# arduinoRGBkaleidoscopeCkt1_v4.net
KiCad netlist of a schematic drawn in EAGLE
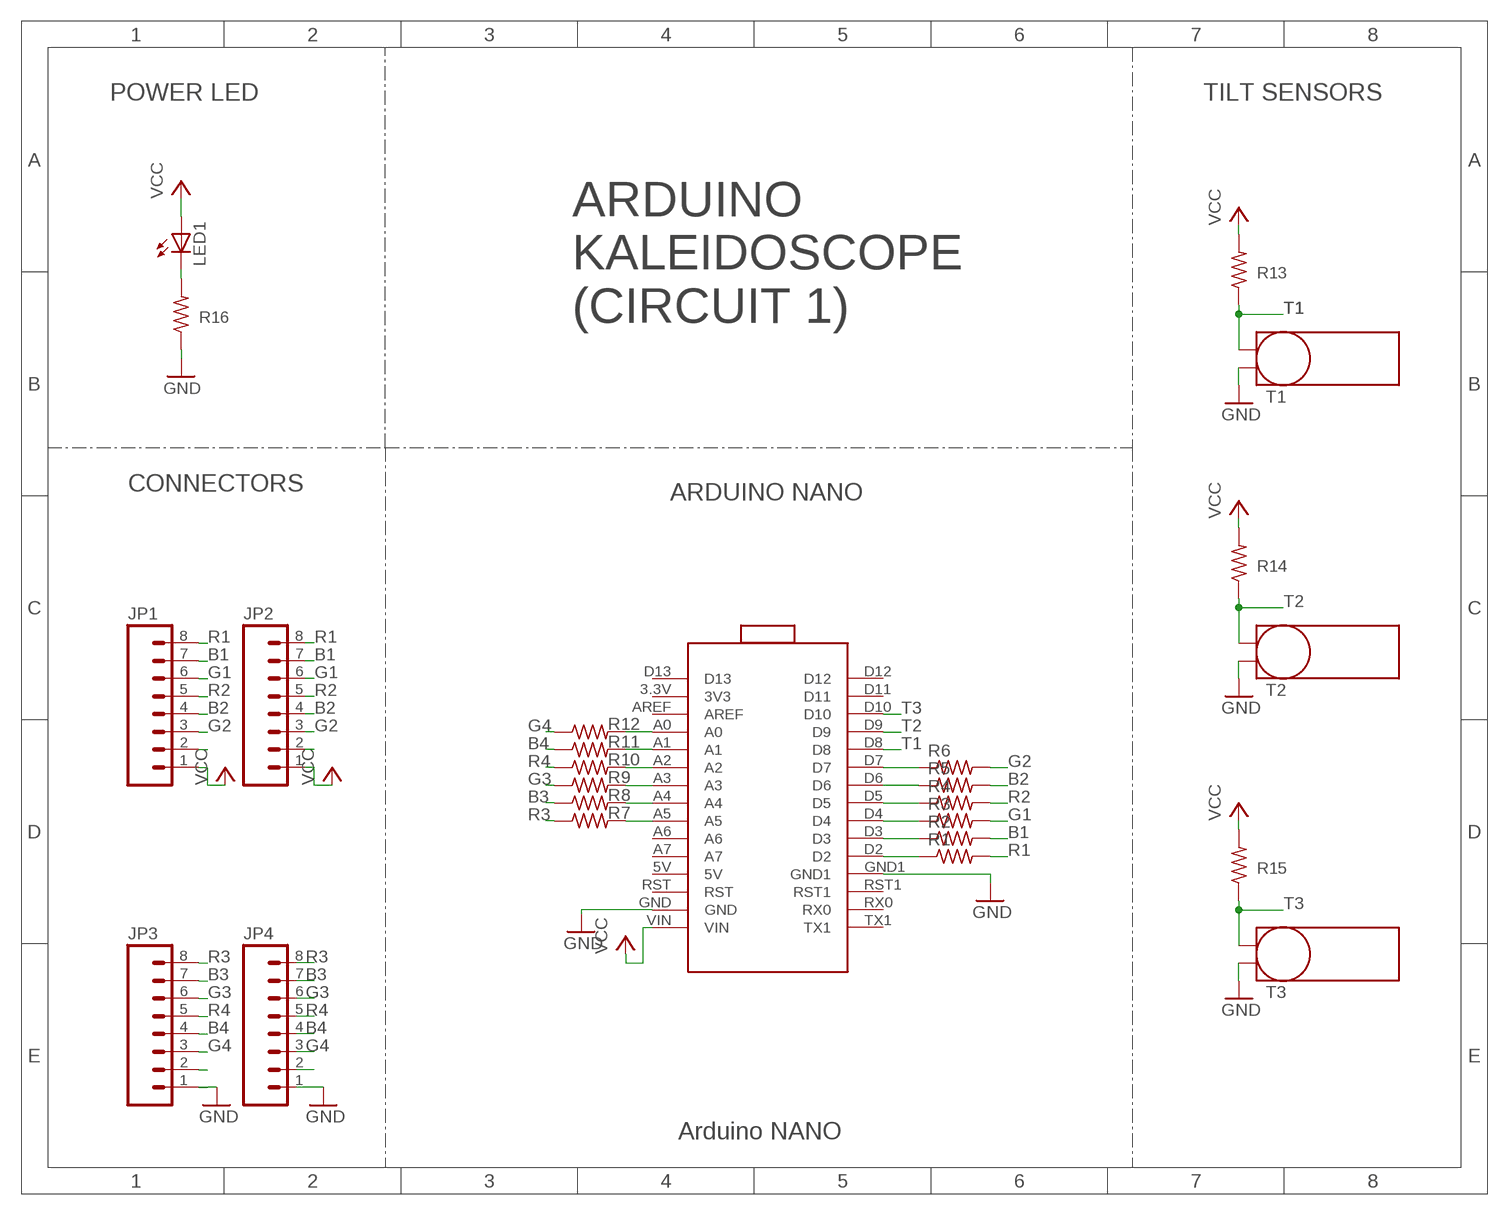
[diagram p0: schematic, sheet 1]

(export (version "E")
  (design (tool "Eeschema 10.0.6"))
  (components
    (comp (ref "JP1")
      (value "M081X08")
      (footprint "eagle-import:1X08")
      (libsource (lib "eagle-import") (part "M081X08"))
    )
    (comp (ref "JP2")
      (value "M081X08")
      (footprint "eagle-import:1X08")
      (libsource (lib "eagle-import") (part "M081X08"))
    )
    (comp (ref "JP3")
      (value "M081X08")
      (footprint "eagle-import:1X08")
      (libsource (lib "eagle-import") (part "M081X08"))
    )
    (comp (ref "JP4")
      (value "M081X08")
      (footprint "eagle-import:1X08")
      (libsource (lib "eagle-import") (part "M081X08"))
    )
    (comp (ref "LED1")
      (value "LED3MM")
      (footprint "eagle-import:LED3MM")
      (libsource (lib "eagle-import") (part "LED3MM"))
    )
    (comp (ref "R1")
      (value "RESISTOR0805")
      (footprint "eagle-import:R0805")
      (libsource (lib "eagle-import") (part "RESISTOR0805"))
    )
    (comp (ref "R2")
      (value "RESISTOR0805")
      (footprint "eagle-import:R0805")
      (libsource (lib "eagle-import") (part "RESISTOR0805"))
    )
    (comp (ref "R3")
      (value "RESISTOR0805")
      (footprint "eagle-import:R0805")
      (libsource (lib "eagle-import") (part "RESISTOR0805"))
    )
    (comp (ref "R4")
      (value "RESISTOR0805")
      (footprint "eagle-import:R0805")
      (libsource (lib "eagle-import") (part "RESISTOR0805"))
    )
    (comp (ref "R5")
      (value "RESISTOR0805")
      (footprint "eagle-import:R0805")
      (libsource (lib "eagle-import") (part "RESISTOR0805"))
    )
    (comp (ref "R6")
      (value "RESISTOR0805")
      (footprint "eagle-import:R0805")
      (libsource (lib "eagle-import") (part "RESISTOR0805"))
    )
    (comp (ref "R7")
      (value "RESISTOR0805")
      (footprint "eagle-import:R0805")
      (libsource (lib "eagle-import") (part "RESISTOR0805"))
    )
    (comp (ref "R8")
      (value "RESISTOR0805")
      (footprint "eagle-import:R0805")
      (libsource (lib "eagle-import") (part "RESISTOR0805"))
    )
    (comp (ref "R9")
      (value "RESISTOR0805")
      (footprint "eagle-import:R0805")
      (libsource (lib "eagle-import") (part "RESISTOR0805"))
    )
    (comp (ref "R10")
      (value "RESISTOR0805")
      (footprint "eagle-import:R0805")
      (libsource (lib "eagle-import") (part "RESISTOR0805"))
    )
    (comp (ref "R11")
      (value "RESISTOR0805")
      (footprint "eagle-import:R0805")
      (libsource (lib "eagle-import") (part "RESISTOR0805"))
    )
    (comp (ref "R12")
      (value "RESISTOR0805")
      (footprint "eagle-import:R0805")
      (libsource (lib "eagle-import") (part "RESISTOR0805"))
    )
    (comp (ref "R13")
      (value "R-US_0204/7")
      (footprint "eagle-import:0204_7")
      (libsource (lib "eagle-import") (part "R-US_0204/7"))
    )
    (comp (ref "R14")
      (value "R-US_0204/7")
      (footprint "eagle-import:0204_7")
      (libsource (lib "eagle-import") (part "R-US_0204/7"))
    )
    (comp (ref "R15")
      (value "R-US_0204/7")
      (footprint "eagle-import:0204_7")
      (libsource (lib "eagle-import") (part "R-US_0204/7"))
    )
    (comp (ref "R16")
      (value "R-US_0204/7")
      (footprint "eagle-import:0204_7")
      (libsource (lib "eagle-import") (part "R-US_0204/7"))
    )
    (comp (ref "T1")
      (value "TILTSENSORE2.5-7")
      (footprint "eagle-import:TILTSENSOR")
      (libsource (lib "eagle-import") (part "TILTSENSORE2.5-7"))
    )
    (comp (ref "T2")
      (value "TILTSENSORE2.5-7")
      (footprint "eagle-import:TILTSENSOR")
      (libsource (lib "eagle-import") (part "TILTSENSORE2.5-7"))
    )
    (comp (ref "T3")
      (value "TILTSENSORE2.5-7")
      (footprint "eagle-import:TILTSENSOR")
      (libsource (lib "eagle-import") (part "TILTSENSORE2.5-7"))
    )
    (comp (ref "U$2")
      (value "NANO")
      (footprint "eagle-import:NANO-2")
      (libsource (lib "eagle-import") (part "NANO"))
    )
  )
  (nets
    (net (code "1") (name "/B1") (class "Default")
      (node (ref "JP1") (pin "7") (pinfunction "7_7") (pintype "passive"))
      (node (ref "JP2") (pin "7") (pinfunction "7_7") (pintype "passive"))
      (node (ref "R2") (pin "2") (pinfunction "2_2") (pintype "passive"))
    )
    (net (code "2") (name "/B2") (class "Default")
      (node (ref "JP1") (pin "4") (pinfunction "4_4") (pintype "passive"))
      (node (ref "JP2") (pin "4") (pinfunction "4_4") (pintype "passive"))
      (node (ref "R5") (pin "2") (pinfunction "2_2") (pintype "passive"))
    )
    (net (code "3") (name "/B3") (class "Default")
      (node (ref "JP3") (pin "7") (pinfunction "7_7") (pintype "passive"))
      (node (ref "JP4") (pin "7") (pinfunction "7_7") (pintype "passive"))
      (node (ref "R8") (pin "1") (pinfunction "1_1") (pintype "passive"))
    )
    (net (code "4") (name "/B4") (class "Default")
      (node (ref "JP3") (pin "4") (pinfunction "4_4") (pintype "passive"))
      (node (ref "JP4") (pin "4") (pinfunction "4_4") (pintype "passive"))
      (node (ref "R11") (pin "1") (pinfunction "1_1") (pintype "passive"))
    )
    (net (code "5") (name "/G1") (class "Default")
      (node (ref "JP1") (pin "6") (pinfunction "6_6") (pintype "passive"))
      (node (ref "JP2") (pin "6") (pinfunction "6_6") (pintype "passive"))
      (node (ref "R3") (pin "2") (pinfunction "2_2") (pintype "passive"))
    )
    (net (code "6") (name "/G2") (class "Default")
      (node (ref "JP1") (pin "3") (pinfunction "3_3") (pintype "passive"))
      (node (ref "JP2") (pin "3") (pinfunction "3_3") (pintype "passive"))
      (node (ref "R6") (pin "2") (pinfunction "2_2") (pintype "passive"))
    )
    (net (code "7") (name "/G3") (class "Default")
      (node (ref "JP3") (pin "6") (pinfunction "6_6") (pintype "passive"))
      (node (ref "JP4") (pin "6") (pinfunction "6_6") (pintype "passive"))
      (node (ref "R9") (pin "1") (pinfunction "1_1") (pintype "passive"))
    )
    (net (code "8") (name "/G4") (class "Default")
      (node (ref "JP3") (pin "3") (pinfunction "3_3") (pintype "passive"))
      (node (ref "JP4") (pin "3") (pinfunction "3_3") (pintype "passive"))
      (node (ref "R12") (pin "1") (pinfunction "1_1") (pintype "passive"))
    )
    (net (code "9") (name "/R1") (class "Default")
      (node (ref "JP1") (pin "8") (pinfunction "8_8") (pintype "passive"))
      (node (ref "JP2") (pin "8") (pinfunction "8_8") (pintype "passive"))
      (node (ref "R1") (pin "2") (pinfunction "2_2") (pintype "passive"))
    )
    (net (code "10") (name "/R2") (class "Default")
      (node (ref "JP1") (pin "5") (pinfunction "5_5") (pintype "passive"))
      (node (ref "JP2") (pin "5") (pinfunction "5_5") (pintype "passive"))
      (node (ref "R4") (pin "2") (pinfunction "2_2") (pintype "passive"))
    )
    (net (code "11") (name "/R3") (class "Default")
      (node (ref "JP3") (pin "8") (pinfunction "8_8") (pintype "passive"))
      (node (ref "JP4") (pin "8") (pinfunction "8_8") (pintype "passive"))
      (node (ref "R7") (pin "1") (pinfunction "1_1") (pintype "passive"))
    )
    (net (code "12") (name "/R4") (class "Default")
      (node (ref "JP3") (pin "5") (pinfunction "5_5") (pintype "passive"))
      (node (ref "JP4") (pin "5") (pinfunction "5_5") (pintype "passive"))
      (node (ref "R10") (pin "1") (pinfunction "1_1") (pintype "passive"))
    )
    (net (code "13") (name "/T1") (class "Default")
      (node (ref "R13") (pin "1") (pinfunction "1_1") (pintype "passive"))
      (node (ref "T1") (pin "+") (pinfunction "+_+") (pintype "passive"))
      (node (ref "U$2") (pin "D8") (pinfunction "D8_D8") (pintype "bidirectional"))
    )
    (net (code "14") (name "/T2") (class "Default")
      (node (ref "R14") (pin "1") (pinfunction "1_1") (pintype "passive"))
      (node (ref "T2") (pin "+") (pinfunction "+_+") (pintype "passive"))
      (node (ref "U$2") (pin "D9") (pinfunction "D9_D9") (pintype "bidirectional"))
    )
    (net (code "15") (name "/T3") (class "Default")
      (node (ref "R15") (pin "1") (pinfunction "1_1") (pintype "passive"))
      (node (ref "T3") (pin "+") (pinfunction "+_+") (pintype "passive"))
      (node (ref "U$2") (pin "D10") (pinfunction "D10_D10") (pintype "bidirectional"))
    )
    (net (code "16") (name "GND") (class "Default")
      (node (ref "JP3") (pin "1") (pinfunction "1_1") (pintype "passive"))
      (node (ref "JP4") (pin "1") (pinfunction "1_1") (pintype "passive"))
      (node (ref "R16") (pin "1") (pinfunction "1_1") (pintype "passive"))
      (node (ref "T1") (pin "-") (pinfunction "-_-") (pintype "passive"))
      (node (ref "T2") (pin "-") (pinfunction "-_-") (pintype "passive"))
      (node (ref "T3") (pin "-") (pinfunction "-_-") (pintype "passive"))
      (node (ref "U$2") (pin "GND") (pinfunction "GND_GND") (pintype "bidirectional"))
      (node (ref "U$2") (pin "GND1") (pinfunction "GND1_GND1") (pintype "bidirectional"))
    )
    (net (code "17") (name "Net-(LED1-C)") (class "Default")
      (node (ref "LED1") (pin "K") (pinfunction "C_K") (pintype "passive"))
      (node (ref "R16") (pin "2") (pinfunction "2_2") (pintype "passive"))
    )
    (net (code "18") (name "Net-(R1-Pad1)") (class "Default")
      (node (ref "R1") (pin "1") (pinfunction "1_1") (pintype "passive"))
      (node (ref "U$2") (pin "D2") (pinfunction "D2_D2") (pintype "bidirectional"))
    )
    (net (code "19") (name "Net-(R2-Pad1)") (class "Default")
      (node (ref "R2") (pin "1") (pinfunction "1_1") (pintype "passive"))
      (node (ref "U$2") (pin "D3") (pinfunction "D3_D3") (pintype "bidirectional"))
    )
    (net (code "20") (name "Net-(R3-Pad1)") (class "Default")
      (node (ref "R3") (pin "1") (pinfunction "1_1") (pintype "passive"))
      (node (ref "U$2") (pin "D4") (pinfunction "D4_D4") (pintype "bidirectional"))
    )
    (net (code "21") (name "Net-(R4-Pad1)") (class "Default")
      (node (ref "R4") (pin "1") (pinfunction "1_1") (pintype "passive"))
      (node (ref "U$2") (pin "D5") (pinfunction "D5_D5") (pintype "bidirectional"))
    )
    (net (code "22") (name "Net-(R5-Pad1)") (class "Default")
      (node (ref "R5") (pin "1") (pinfunction "1_1") (pintype "passive"))
      (node (ref "U$2") (pin "D6") (pinfunction "D6_D6") (pintype "bidirectional"))
    )
    (net (code "23") (name "Net-(R6-Pad1)") (class "Default")
      (node (ref "R6") (pin "1") (pinfunction "1_1") (pintype "passive"))
      (node (ref "U$2") (pin "D7") (pinfunction "D7_D7") (pintype "bidirectional"))
    )
    (net (code "24") (name "Net-(R7-Pad2)") (class "Default")
      (node (ref "R7") (pin "2") (pinfunction "2_2") (pintype "passive"))
      (node (ref "U$2") (pin "A5") (pinfunction "A5_A5") (pintype "bidirectional"))
    )
    (net (code "25") (name "Net-(R8-Pad2)") (class "Default")
      (node (ref "R8") (pin "2") (pinfunction "2_2") (pintype "passive"))
      (node (ref "U$2") (pin "A4") (pinfunction "A4_A4") (pintype "bidirectional"))
    )
    (net (code "26") (name "Net-(R9-Pad2)") (class "Default")
      (node (ref "R9") (pin "2") (pinfunction "2_2") (pintype "passive"))
      (node (ref "U$2") (pin "A3") (pinfunction "A3_A3") (pintype "bidirectional"))
    )
    (net (code "27") (name "Net-(R10-Pad2)") (class "Default")
      (node (ref "R10") (pin "2") (pinfunction "2_2") (pintype "passive"))
      (node (ref "U$2") (pin "A2") (pinfunction "A2_A2") (pintype "bidirectional"))
    )
    (net (code "28") (name "Net-(R11-Pad2)") (class "Default")
      (node (ref "R11") (pin "2") (pinfunction "2_2") (pintype "passive"))
      (node (ref "U$2") (pin "A1") (pinfunction "A1_A1") (pintype "bidirectional"))
    )
    (net (code "29") (name "Net-(R12-Pad2)") (class "Default")
      (node (ref "R12") (pin "2") (pinfunction "2_2") (pintype "passive"))
      (node (ref "U$2") (pin "A0") (pinfunction "A0_A0") (pintype "bidirectional"))
    )
    (net (code "30") (name "VCC") (class "Default")
      (node (ref "JP1") (pin "1") (pinfunction "1_1") (pintype "passive"))
      (node (ref "JP2") (pin "1") (pinfunction "1_1") (pintype "passive"))
      (node (ref "LED1") (pin "A") (pinfunction "A_A") (pintype "passive"))
      (node (ref "R13") (pin "2") (pinfunction "2_2") (pintype "passive"))
      (node (ref "R14") (pin "2") (pinfunction "2_2") (pintype "passive"))
      (node (ref "R15") (pin "2") (pinfunction "2_2") (pintype "passive"))
      (node (ref "U$2") (pin "VIN") (pinfunction "VIN_VIN") (pintype "bidirectional"))
    )
    (net (code "31") (name "unconnected-(JP1-Pad2)") (class "Default")
      (node (ref "JP1") (pin "2") (pinfunction "2_2") (pintype "passive"))
    )
    (net (code "32") (name "unconnected-(JP2-Pad2)") (class "Default")
      (node (ref "JP2") (pin "2") (pinfunction "2_2") (pintype "passive"))
    )
    (net (code "33") (name "unconnected-(JP3-Pad2)") (class "Default")
      (node (ref "JP3") (pin "2") (pinfunction "2_2") (pintype "passive"))
    )
    (net (code "34") (name "unconnected-(JP4-Pad2)") (class "Default")
      (node (ref "JP4") (pin "2") (pinfunction "2_2") (pintype "passive"))
    )
    (net (code "35") (name "unconnected-(U$2-3V3-Pad3.3V)") (class "Default")
      (node (ref "U$2") (pin "3.3V") (pinfunction "3V3_3.3V") (pintype "bidirectional"))
    )
    (net (code "36") (name "unconnected-(U$2-Pad5V)") (class "Default")
      (node (ref "U$2") (pin "5V") (pinfunction "5V_5V") (pintype "bidirectional"))
    )
    (net (code "37") (name "unconnected-(U$2-PadA6)") (class "Default")
      (node (ref "U$2") (pin "A6") (pinfunction "A6_A6") (pintype "bidirectional"))
    )
    (net (code "38") (name "unconnected-(U$2-PadA7)") (class "Default")
      (node (ref "U$2") (pin "A7") (pinfunction "A7_A7") (pintype "bidirectional"))
    )
    (net (code "39") (name "unconnected-(U$2-PadAREF)") (class "Default")
      (node (ref "U$2") (pin "AREF") (pinfunction "AREF_AREF") (pintype "bidirectional"))
    )
    (net (code "40") (name "unconnected-(U$2-PadD11)") (class "Default")
      (node (ref "U$2") (pin "D11") (pinfunction "D11_D11") (pintype "bidirectional"))
    )
    (net (code "41") (name "unconnected-(U$2-PadD12)") (class "Default")
      (node (ref "U$2") (pin "D12") (pinfunction "D12_D12") (pintype "bidirectional"))
    )
    (net (code "42") (name "unconnected-(U$2-PadD13)") (class "Default")
      (node (ref "U$2") (pin "D13") (pinfunction "D13_D13") (pintype "bidirectional"))
    )
    (net (code "43") (name "unconnected-(U$2-PadRST)") (class "Default")
      (node (ref "U$2") (pin "RST") (pinfunction "RST_RST") (pintype "bidirectional"))
    )
    (net (code "44") (name "unconnected-(U$2-PadRST1)") (class "Default")
      (node (ref "U$2") (pin "RST1") (pinfunction "RST1_RST1") (pintype "bidirectional"))
    )
    (net (code "45") (name "unconnected-(U$2-PadRX0)") (class "Default")
      (node (ref "U$2") (pin "RX0") (pinfunction "RX0_RX0") (pintype "bidirectional"))
    )
    (net (code "46") (name "unconnected-(U$2-PadTX1)") (class "Default")
      (node (ref "U$2") (pin "TX1") (pinfunction "TX1_TX1") (pintype "bidirectional"))
    )
  )
)
